# dragonboard.net
KiCad netlist of a schematic drawn in Altium Designer
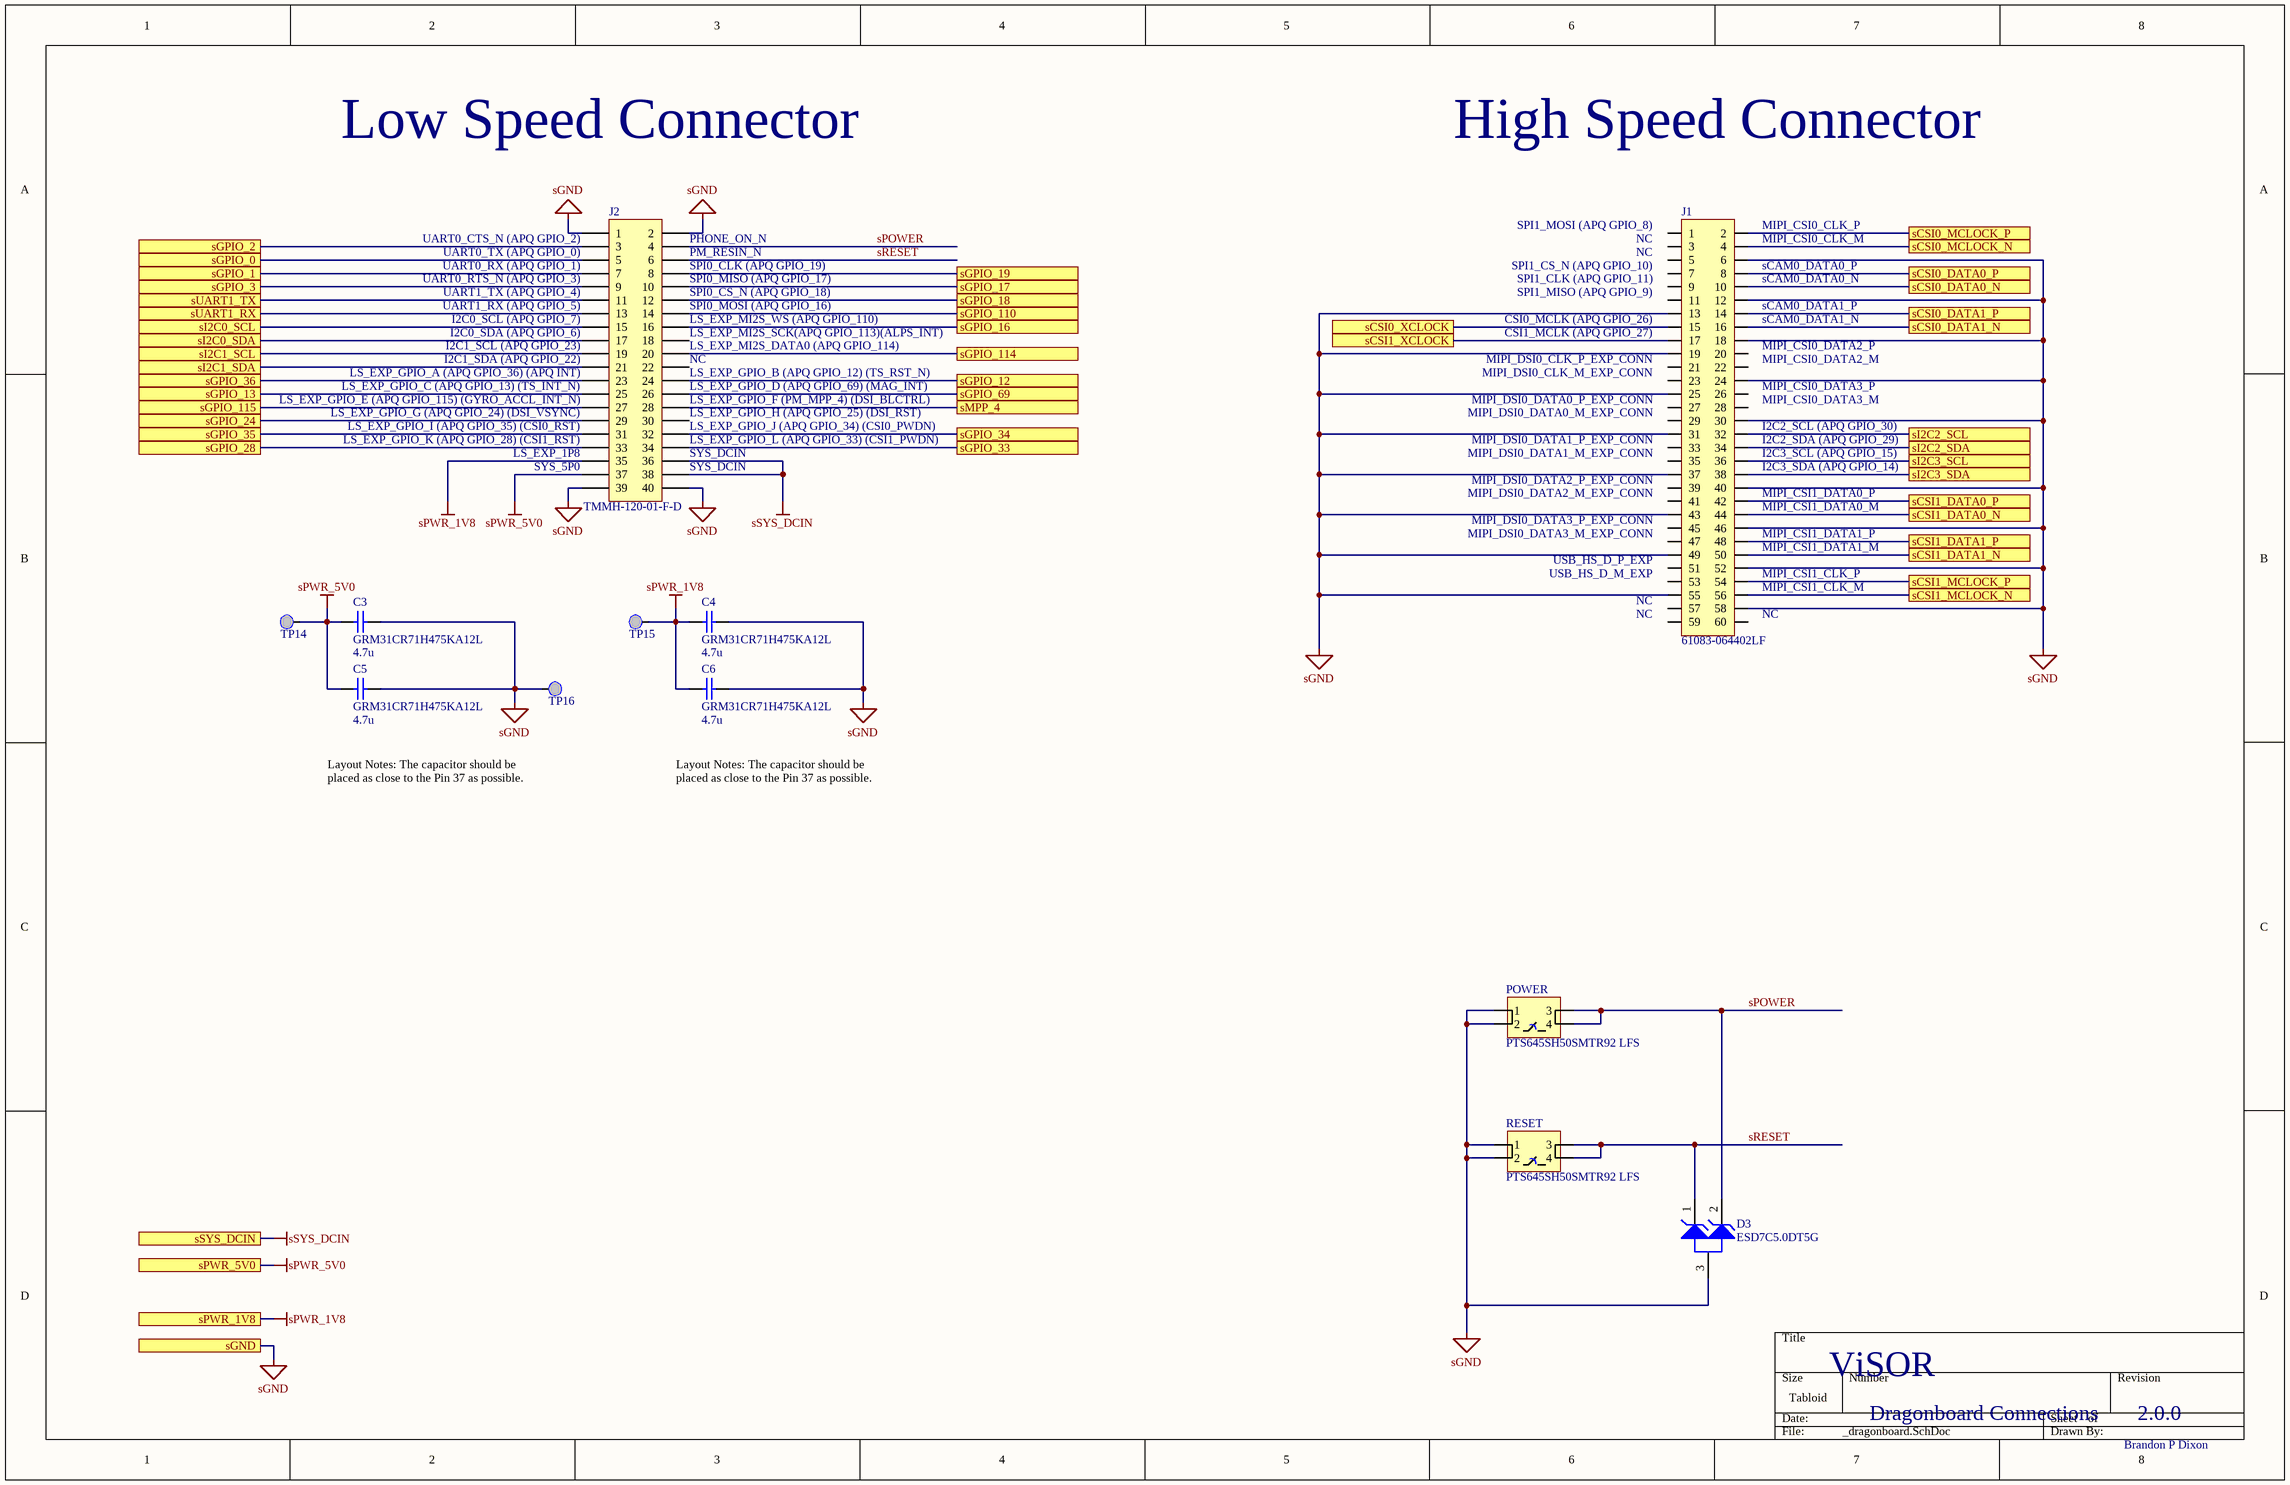
[diagram p0: _dragonboard.SchDoc]

(export (version "E")
  (design (tool "Eeschema 10.0.6"))
  (components
    (comp (ref "C3")
      (value "GRM31CR71H475KA12L")
      (footprint "1206")
      (description "-55-125C, 3216, 50V, X7R, ±10%")
      (fields (field (name "ALTIUM_VALUE") "4.7u"))
      (libsource (lib "standard_capacitors") (part "GRM31CR71HxxxKdddd"))
    )
    (comp (ref "C4")
      (value "GRM31CR71H475KA12L")
      (footprint "1206")
      (description "-55-125C, 3216, 50V, X7R, ±10%")
      (fields (field (name "ALTIUM_VALUE") "4.7u"))
      (libsource (lib "standard_capacitors") (part "GRM31CR71HxxxKdddd"))
    )
    (comp (ref "C5")
      (value "GRM31CR71H475KA12L")
      (footprint "1206")
      (description "-55-125C, 3216, 50V, X7R, ±10%")
      (fields (field (name "ALTIUM_VALUE") "4.7u"))
      (libsource (lib "standard_capacitors") (part "GRM31CR71HxxxKdddd"))
    )
    (comp (ref "C6")
      (value "GRM31CR71H475KA12L")
      (footprint "1206")
      (description "-55-125C, 3216, 50V, X7R, ±10%")
      (fields (field (name "ALTIUM_VALUE") "4.7u"))
      (libsource (lib "standard_capacitors") (part "GRM31CR71HxxxKdddd"))
    )
    (comp (ref "D3")
      (value "ESD7C5.0DT5G")
      (footprint "ONSC-SOT-723-3-631AA-01_V")
      (fields (field (name "MANUFACTURER") "On Semiconductor"))
      (libsource (lib "Altium Content Vault") (part "ONSC-K1K2A3-3"))
    )
    (comp (ref "J1")
      (value "61083-064402LF")
      (footprint "61083-064402LF")
      (libsource (lib "fci") (part "61083-064402LF"))
    )
    (comp (ref "J2")
      (value "TMMH-120-01-F-D")
      (footprint "HDR2X20.Metric")
      (description "Header, 2x20-Pin, Dual row, Metric")
      (libsource (lib "samtec") (part "TMMH-120-01-F-D"))
    )
    (comp (ref "POWER")
      (value "PTS645SH50SMTR92 LFS")
      (footprint "PTS645SH50SMTR92 LFS")
      (description "Tactile Switch")
      (libsource (lib "candk") (part "PTS645SH50SMTR92 LFS"))
    )
    (comp (ref "RESET")
      (value "PTS645SH50SMTR92 LFS")
      (footprint "PTS645SH50SMTR92 LFS")
      (description "Tactile Switch")
      (libsource (lib "candk") (part "PTS645SH50SMTR92 LFS"))
    )
    (comp (ref "TP14") (value "TP") (footprint "TP_TH") (libsource (lib "common") (part "TP")))
    (comp (ref "TP15") (value "TP") (footprint "TP_TH") (libsource (lib "common") (part "TP")))
    (comp (ref "TP16") (value "TP") (footprint "TP_TH") (libsource (lib "common") (part "TP")))
  )
  (nets
    (net (code "1") (name "/sCSI0_DATA0_N") (class "Default")
      (node (ref "J1") (pin "10") (pinfunction "10_10") (pintype "passive"))
    )
    (net (code "2") (name "/sCSI0_DATA0_P") (class "Default")
      (node (ref "J1") (pin "8") (pinfunction "8_8") (pintype "passive"))
    )
    (net (code "3") (name "/sCSI0_DATA1_N") (class "Default")
      (node (ref "J1") (pin "16") (pinfunction "16_16") (pintype "passive"))
    )
    (net (code "4") (name "/sCSI0_DATA1_P") (class "Default")
      (node (ref "J1") (pin "14") (pinfunction "14_14") (pintype "passive"))
    )
    (net (code "5") (name "/sCSI0_MCLOCK_N") (class "Default")
      (node (ref "J1") (pin "4") (pinfunction "4_4") (pintype "passive"))
    )
    (net (code "6") (name "/sCSI0_MCLOCK_P") (class "Default")
      (node (ref "J1") (pin "2") (pinfunction "2_2") (pintype "passive"))
    )
    (net (code "7") (name "/sCSI0_XCLOCK") (class "Default")
      (node (ref "J1") (pin "15") (pinfunction "15_15") (pintype "passive"))
    )
    (net (code "8") (name "/sCSI1_DATA0_N") (class "Default")
      (node (ref "J1") (pin "44") (pinfunction "44_44") (pintype "passive"))
    )
    (net (code "9") (name "/sCSI1_DATA0_P") (class "Default")
      (node (ref "J1") (pin "42") (pinfunction "42_42") (pintype "passive"))
    )
    (net (code "10") (name "/sCSI1_DATA1_N") (class "Default")
      (node (ref "J1") (pin "50") (pinfunction "50_50") (pintype "passive"))
    )
    (net (code "11") (name "/sCSI1_DATA1_P") (class "Default")
      (node (ref "J1") (pin "48") (pinfunction "48_48") (pintype "passive"))
    )
    (net (code "12") (name "/sCSI1_MCLOCK_N") (class "Default")
      (node (ref "J1") (pin "56") (pinfunction "56_56") (pintype "passive"))
    )
    (net (code "13") (name "/sCSI1_MCLOCK_P") (class "Default")
      (node (ref "J1") (pin "54") (pinfunction "54_54") (pintype "passive"))
    )
    (net (code "14") (name "/sCSI1_XCLOCK") (class "Default")
      (node (ref "J1") (pin "17") (pinfunction "17_17") (pintype "passive"))
    )
    (net (code "15") (name "/sGPIO_0") (class "Default")
      (node (ref "J2") (pin "5") (pinfunction "5_5") (pintype "passive"))
    )
    (net (code "16") (name "/sGPIO_1") (class "Default")
      (node (ref "J2") (pin "7") (pinfunction "7_7") (pintype "passive"))
    )
    (net (code "17") (name "/sGPIO_2") (class "Default")
      (node (ref "J2") (pin "3") (pinfunction "3_3") (pintype "passive"))
    )
    (net (code "18") (name "/sGPIO_3") (class "Default")
      (node (ref "J2") (pin "9") (pinfunction "9_9") (pintype "passive"))
    )
    (net (code "19") (name "/sGPIO_12") (class "Default")
      (node (ref "J2") (pin "24") (pinfunction "24_24") (pintype "passive"))
    )
    (net (code "20") (name "/sGPIO_13") (class "Default")
      (node (ref "J2") (pin "25") (pinfunction "25_25") (pintype "passive"))
    )
    (net (code "21") (name "/sGPIO_16") (class "Default")
      (node (ref "J2") (pin "16") (pinfunction "16_16") (pintype "passive"))
    )
    (net (code "22") (name "/sGPIO_17") (class "Default")
      (node (ref "J2") (pin "10") (pinfunction "10_10") (pintype "passive"))
    )
    (net (code "23") (name "/sGPIO_18") (class "Default")
      (node (ref "J2") (pin "12") (pinfunction "12_12") (pintype "passive"))
    )
    (net (code "24") (name "/sGPIO_19") (class "Default")
      (node (ref "J2") (pin "8") (pinfunction "8_8") (pintype "passive"))
    )
    (net (code "25") (name "/sGPIO_24") (class "Default")
      (node (ref "J2") (pin "29") (pinfunction "29_29") (pintype "passive"))
    )
    (net (code "26") (name "/sGPIO_28") (class "Default")
      (node (ref "J2") (pin "33") (pinfunction "33_33") (pintype "passive"))
    )
    (net (code "27") (name "/sGPIO_33") (class "Default")
      (node (ref "J2") (pin "34") (pinfunction "34_34") (pintype "passive"))
    )
    (net (code "28") (name "/sGPIO_34") (class "Default")
      (node (ref "J2") (pin "32") (pinfunction "32_32") (pintype "passive"))
    )
    (net (code "29") (name "/sGPIO_35") (class "Default")
      (node (ref "J2") (pin "31") (pinfunction "31_31") (pintype "passive"))
    )
    (net (code "30") (name "/sGPIO_36") (class "Default")
      (node (ref "J2") (pin "23") (pinfunction "23_23") (pintype "passive"))
    )
    (net (code "31") (name "/sGPIO_69") (class "Default")
      (node (ref "J2") (pin "26") (pinfunction "26_26") (pintype "passive"))
    )
    (net (code "32") (name "/sGPIO_110") (class "Default")
      (node (ref "J2") (pin "14") (pinfunction "14_14") (pintype "passive"))
    )
    (net (code "33") (name "/sGPIO_114") (class "Default")
      (node (ref "J2") (pin "20") (pinfunction "20_20") (pintype "passive"))
    )
    (net (code "34") (name "/sGPIO_115") (class "Default")
      (node (ref "J2") (pin "27") (pinfunction "27_27") (pintype "passive"))
    )
    (net (code "35") (name "/sI2C0_SCL") (class "Default")
      (node (ref "J2") (pin "15") (pinfunction "15_15") (pintype "passive"))
    )
    (net (code "36") (name "/sI2C0_SDA") (class "Default")
      (node (ref "J2") (pin "17") (pinfunction "17_17") (pintype "passive"))
    )
    (net (code "37") (name "/sI2C1_SCL") (class "Default")
      (node (ref "J2") (pin "19") (pinfunction "19_19") (pintype "passive"))
    )
    (net (code "38") (name "/sI2C1_SDA") (class "Default")
      (node (ref "J2") (pin "21") (pinfunction "21_21") (pintype "passive"))
    )
    (net (code "39") (name "/sI2C2_SCL") (class "Default")
      (node (ref "J1") (pin "32") (pinfunction "32_32") (pintype "passive"))
    )
    (net (code "40") (name "/sI2C2_SDA") (class "Default")
      (node (ref "J1") (pin "34") (pinfunction "34_34") (pintype "passive"))
    )
    (net (code "41") (name "/sI2C3_SCL") (class "Default")
      (node (ref "J1") (pin "36") (pinfunction "36_36") (pintype "passive"))
    )
    (net (code "42") (name "/sI2C3_SDA") (class "Default")
      (node (ref "J1") (pin "38") (pinfunction "38_38") (pintype "passive"))
    )
    (net (code "43") (name "/sMPP_4") (class "Default")
      (node (ref "J2") (pin "28") (pinfunction "28_28") (pintype "passive"))
    )
    (net (code "44") (name "/sPOWER") (class "Default")
      (node (ref "D3") (pin "2") (pinfunction "K2_2") (pintype "passive"))
      (node (ref "J2") (pin "4") (pinfunction "4_4") (pintype "passive"))
      (node (ref "POWER") (pin "3") (pinfunction "3_3") (pintype "passive"))
      (node (ref "POWER") (pin "4") (pinfunction "4_4") (pintype "passive"))
    )
    (net (code "45") (name "/sRESET") (class "Default")
      (node (ref "D3") (pin "1") (pinfunction "K1_1") (pintype "passive"))
      (node (ref "J2") (pin "6") (pinfunction "6_6") (pintype "passive"))
      (node (ref "RESET") (pin "3") (pinfunction "3_3") (pintype "passive"))
      (node (ref "RESET") (pin "4") (pinfunction "4_4") (pintype "passive"))
    )
    (net (code "46") (name "/sUART1_RX") (class "Default")
      (node (ref "J2") (pin "13") (pinfunction "13_13") (pintype "passive"))
    )
    (net (code "47") (name "/sUART1_TX") (class "Default")
      (node (ref "J2") (pin "11") (pinfunction "11_11") (pintype "passive"))
    )
    (net (code "48") (name "sGND") (class "Default")
      (node (ref "C3") (pin "1") (pinfunction "1_1") (pintype "passive"))
      (node (ref "C4") (pin "1") (pinfunction "1_1") (pintype "passive"))
      (node (ref "C5") (pin "1") (pinfunction "1_1") (pintype "passive"))
      (node (ref "C6") (pin "1") (pinfunction "1_1") (pintype "passive"))
      (node (ref "D3") (pin "3") (pinfunction "A_3") (pintype "passive"))
      (node (ref "J1") (pin "12") (pinfunction "12_12") (pintype "passive"))
      (node (ref "J1") (pin "13") (pinfunction "13_13") (pintype "passive"))
      (node (ref "J1") (pin "18") (pinfunction "18_18") (pintype "passive"))
      (node (ref "J1") (pin "19") (pinfunction "19_19") (pintype "passive"))
      (node (ref "J1") (pin "24") (pinfunction "24_24") (pintype "passive"))
      (node (ref "J1") (pin "25") (pinfunction "25_25") (pintype "passive"))
      (node (ref "J1") (pin "30") (pinfunction "30_30") (pintype "passive"))
      (node (ref "J1") (pin "31") (pinfunction "31_31") (pintype "passive"))
      (node (ref "J1") (pin "37") (pinfunction "37_37") (pintype "passive"))
      (node (ref "J1") (pin "40") (pinfunction "40_40") (pintype "passive"))
      (node (ref "J1") (pin "43") (pinfunction "43_43") (pintype "passive"))
      (node (ref "J1") (pin "46") (pinfunction "46_46") (pintype "passive"))
      (node (ref "J1") (pin "49") (pinfunction "49_49") (pintype "passive"))
      (node (ref "J1") (pin "52") (pinfunction "52_52") (pintype "passive"))
      (node (ref "J1") (pin "55") (pinfunction "55_55") (pintype "passive"))
      (node (ref "J1") (pin "58") (pinfunction "58_58") (pintype "passive"))
      (node (ref "J1") (pin "6") (pinfunction "6_6") (pintype "passive"))
      (node (ref "J2") (pin "1") (pinfunction "1_1") (pintype "passive"))
      (node (ref "J2") (pin "2") (pinfunction "2_2") (pintype "passive"))
      (node (ref "J2") (pin "39") (pinfunction "39_39") (pintype "passive"))
      (node (ref "J2") (pin "40") (pinfunction "40_40") (pintype "passive"))
      (node (ref "POWER") (pin "1") (pinfunction "1_1") (pintype "passive"))
      (node (ref "POWER") (pin "2") (pinfunction "2_2") (pintype "passive"))
      (node (ref "RESET") (pin "1") (pinfunction "1_1") (pintype "passive"))
      (node (ref "RESET") (pin "2") (pinfunction "2_2") (pintype "passive"))
      (node (ref "TP16") (pin "1") (pinfunction "1_1") (pintype "passive"))
    )
    (net (code "49") (name "sPWR_1V8") (class "Default")
      (node (ref "C4") (pin "2") (pinfunction "2_2") (pintype "passive"))
      (node (ref "C6") (pin "2") (pinfunction "2_2") (pintype "passive"))
      (node (ref "J2") (pin "35") (pinfunction "35_35") (pintype "passive"))
      (node (ref "TP15") (pin "1") (pinfunction "1_1") (pintype "passive"))
    )
    (net (code "50") (name "sPWR_5V0") (class "Default")
      (node (ref "C3") (pin "2") (pinfunction "2_2") (pintype "passive"))
      (node (ref "C5") (pin "2") (pinfunction "2_2") (pintype "passive"))
      (node (ref "J2") (pin "37") (pinfunction "37_37") (pintype "passive"))
      (node (ref "TP14") (pin "1") (pinfunction "1_1") (pintype "passive"))
    )
    (net (code "51") (name "sSYS_DCIN") (class "Default")
      (node (ref "J2") (pin "36") (pinfunction "36_36") (pintype "passive"))
      (node (ref "J2") (pin "38") (pinfunction "38_38") (pintype "passive"))
    )
    (net (code "52") (name "unconnected-(J1-Pad1)") (class "Default")
      (node (ref "J1") (pin "1") (pinfunction "1_1") (pintype "passive"))
    )
    (net (code "53") (name "unconnected-(J1-Pad3)") (class "Default")
      (node (ref "J1") (pin "3") (pinfunction "3_3") (pintype "passive"))
    )
    (net (code "54") (name "unconnected-(J1-Pad5)") (class "Default")
      (node (ref "J1") (pin "5") (pinfunction "5_5") (pintype "passive"))
    )
    (net (code "55") (name "unconnected-(J1-Pad7)") (class "Default")
      (node (ref "J1") (pin "7") (pinfunction "7_7") (pintype "passive"))
    )
    (net (code "56") (name "unconnected-(J1-Pad9)") (class "Default")
      (node (ref "J1") (pin "9") (pinfunction "9_9") (pintype "passive"))
    )
    (net (code "57") (name "unconnected-(J1-Pad11)") (class "Default")
      (node (ref "J1") (pin "11") (pinfunction "11_11") (pintype "passive"))
    )
    (net (code "58") (name "unconnected-(J1-Pad20)") (class "Default")
      (node (ref "J1") (pin "20") (pinfunction "20_20") (pintype "passive"))
    )
    (net (code "59") (name "unconnected-(J1-Pad21)") (class "Default")
      (node (ref "J1") (pin "21") (pinfunction "21_21") (pintype "passive"))
    )
    (net (code "60") (name "unconnected-(J1-Pad22)") (class "Default")
      (node (ref "J1") (pin "22") (pinfunction "22_22") (pintype "passive"))
    )
    (net (code "61") (name "unconnected-(J1-Pad23)") (class "Default")
      (node (ref "J1") (pin "23") (pinfunction "23_23") (pintype "passive"))
    )
    (net (code "62") (name "unconnected-(J1-Pad26)") (class "Default")
      (node (ref "J1") (pin "26") (pinfunction "26_26") (pintype "passive"))
    )
    (net (code "63") (name "unconnected-(J1-Pad27)") (class "Default")
      (node (ref "J1") (pin "27") (pinfunction "27_27") (pintype "passive"))
    )
    (net (code "64") (name "unconnected-(J1-Pad28)") (class "Default")
      (node (ref "J1") (pin "28") (pinfunction "28_28") (pintype "passive"))
    )
    (net (code "65") (name "unconnected-(J1-Pad29)") (class "Default")
      (node (ref "J1") (pin "29") (pinfunction "29_29") (pintype "passive"))
    )
    (net (code "66") (name "unconnected-(J1-Pad33)") (class "Default")
      (node (ref "J1") (pin "33") (pinfunction "33_33") (pintype "passive"))
    )
    (net (code "67") (name "unconnected-(J1-Pad35)") (class "Default")
      (node (ref "J1") (pin "35") (pinfunction "35_35") (pintype "passive"))
    )
    (net (code "68") (name "unconnected-(J1-Pad39)") (class "Default")
      (node (ref "J1") (pin "39") (pinfunction "39_39") (pintype "passive"))
    )
    (net (code "69") (name "unconnected-(J1-Pad41)") (class "Default")
      (node (ref "J1") (pin "41") (pinfunction "41_41") (pintype "passive"))
    )
    (net (code "70") (name "unconnected-(J1-Pad45)") (class "Default")
      (node (ref "J1") (pin "45") (pinfunction "45_45") (pintype "passive"))
    )
    (net (code "71") (name "unconnected-(J1-Pad47)") (class "Default")
      (node (ref "J1") (pin "47") (pinfunction "47_47") (pintype "passive"))
    )
    (net (code "72") (name "unconnected-(J1-Pad51)") (class "Default")
      (node (ref "J1") (pin "51") (pinfunction "51_51") (pintype "passive"))
    )
    (net (code "73") (name "unconnected-(J1-Pad53)") (class "Default")
      (node (ref "J1") (pin "53") (pinfunction "53_53") (pintype "passive"))
    )
    (net (code "74") (name "unconnected-(J1-Pad57)") (class "Default")
      (node (ref "J1") (pin "57") (pinfunction "57_57") (pintype "passive"))
    )
    (net (code "75") (name "unconnected-(J1-Pad59)") (class "Default")
      (node (ref "J1") (pin "59") (pinfunction "59_59") (pintype "passive"))
    )
    (net (code "76") (name "unconnected-(J1-Pad60)") (class "Default")
      (node (ref "J1") (pin "60") (pinfunction "60_60") (pintype "passive"))
    )
    (net (code "77") (name "unconnected-(J2-Pad18)") (class "Default")
      (node (ref "J2") (pin "18") (pinfunction "18_18") (pintype "passive"))
    )
    (net (code "78") (name "unconnected-(J2-Pad22)") (class "Default")
      (node (ref "J2") (pin "22") (pinfunction "22_22") (pintype "passive"))
    )
    (net (code "79") (name "unconnected-(J2-Pad30)") (class "Default")
      (node (ref "J2") (pin "30") (pinfunction "30_30") (pintype "passive"))
    )
  )
)
